# OpAmpBreakout-fragmentC.net
KiCad netlist of a schematic drawn in EAGLE
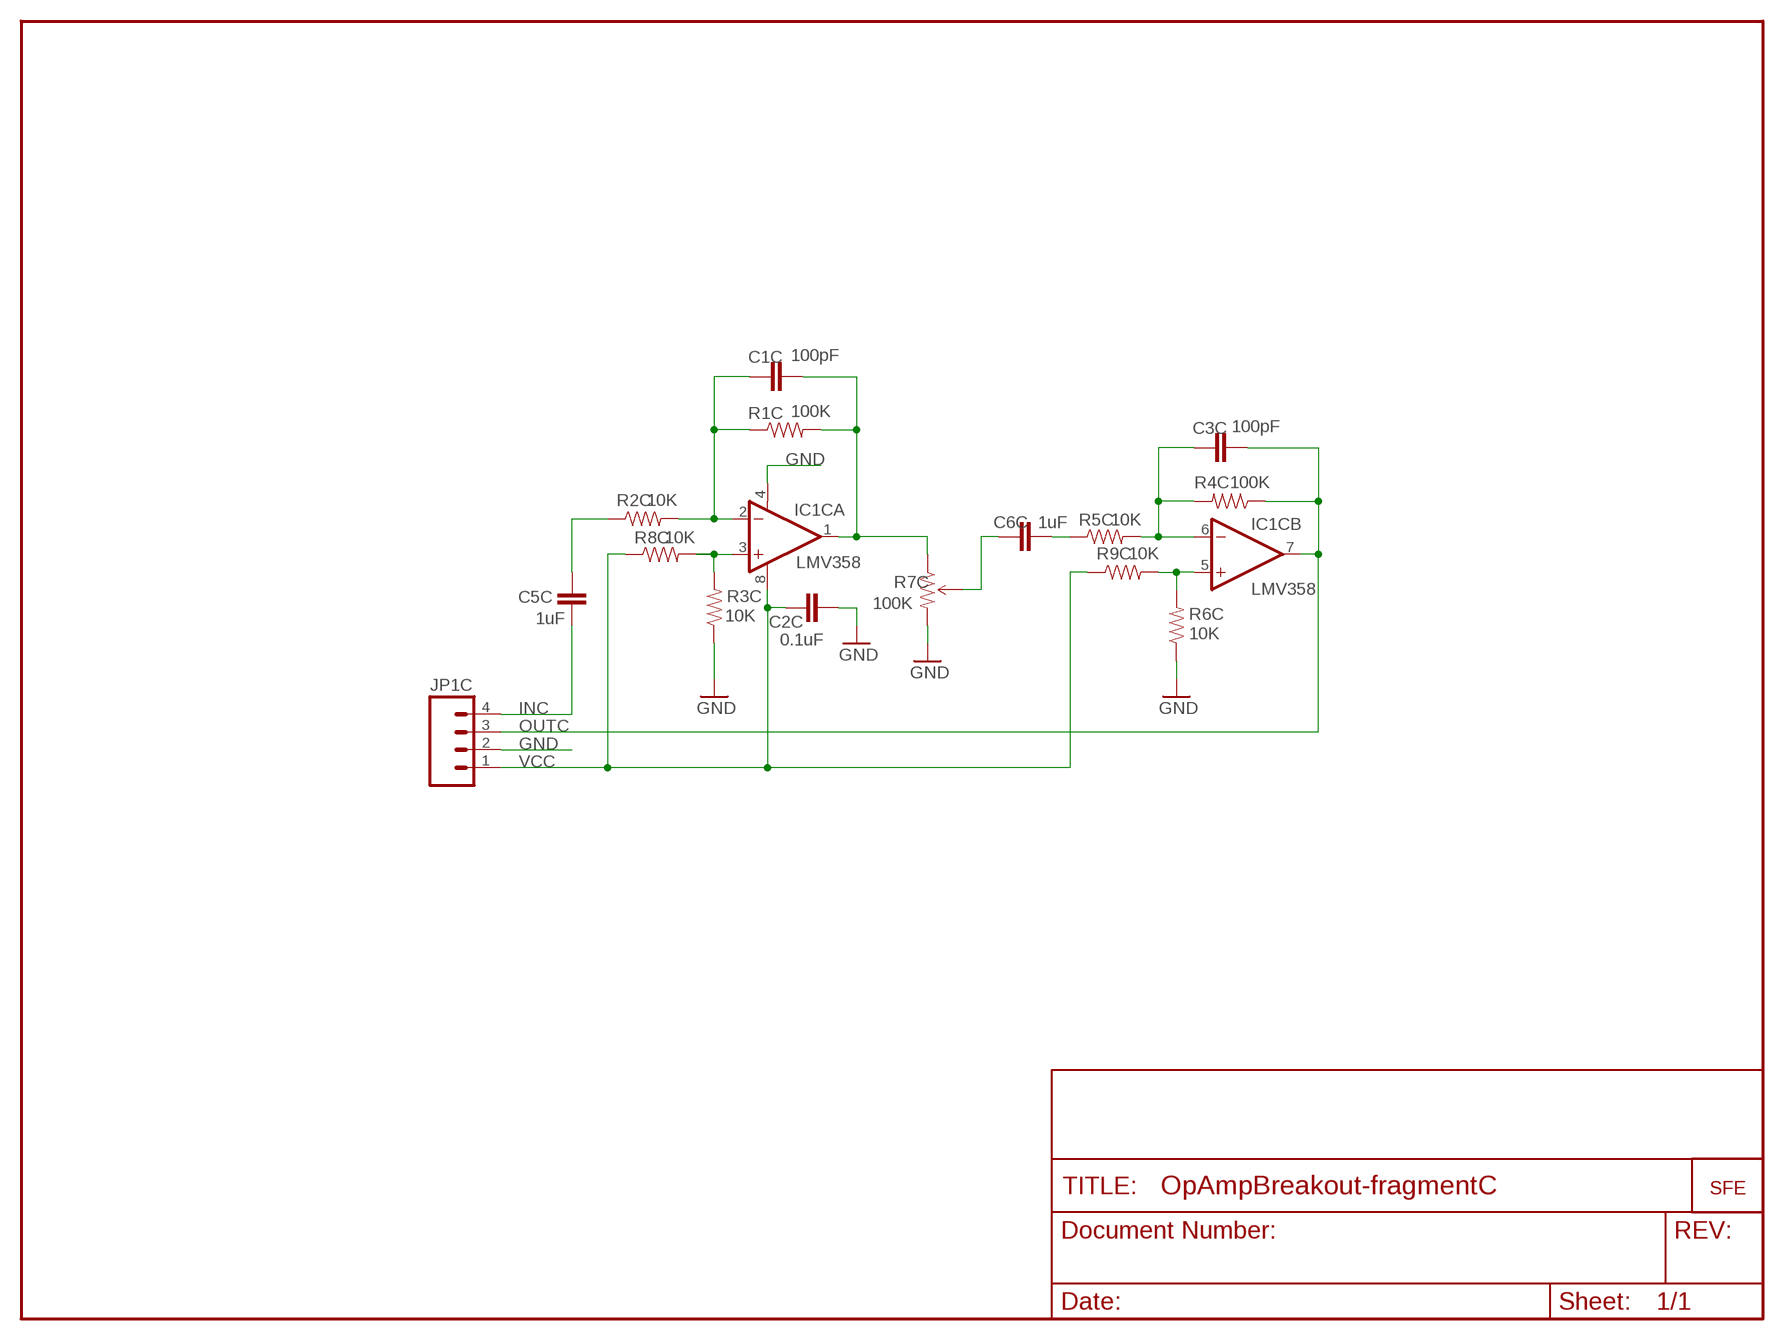
[diagram p0: schematic, sheet 1]

(export (version "E")
  (design (tool "Eeschema 10.0.6"))
  (components
    (comp (ref "C1C")
      (value "100pF")
      (footprint "eagle-import:C0402")
      (libsource (lib "eagle-import") (part "CAP0402"))
    )
    (comp (ref "C2C")
      (value "0.1uF")
      (footprint "eagle-import:C0402")
      (libsource (lib "eagle-import") (part "CAP0402"))
    )
    (comp (ref "C3C")
      (value "100pF")
      (footprint "eagle-import:C0402")
      (libsource (lib "eagle-import") (part "CAP0402"))
    )
    (comp (ref "C5C")
      (value "1uF")
      (footprint "eagle-import:C0402")
      (libsource (lib "eagle-import") (part "CAP0402"))
    )
    (comp (ref "C6C")
      (value "1uF")
      (footprint "eagle-import:C0402")
      (libsource (lib "eagle-import") (part "CAP0402"))
    )
    (comp (ref "IC1C")
      (value "LMV358")
      (footprint "eagle-import:SO08")
      (libsource (lib "eagle-import") (part "OPAMP-DUALU"))
    )
    (comp (ref "JP1C")
      (value "M04PTH")
      (footprint "eagle-import:1X04")
      (libsource (lib "eagle-import") (part "M04PTH"))
    )
    (comp (ref "R1C")
      (value "100K")
      (footprint "eagle-import:C0402")
      (libsource (lib "eagle-import") (part "RESISTOR0402"))
    )
    (comp (ref "R2C")
      (value "10K")
      (footprint "eagle-import:C0402")
      (libsource (lib "eagle-import") (part "RESISTOR0402"))
    )
    (comp (ref "R3C")
      (value "10K")
      (footprint "eagle-import:C0402")
      (libsource (lib "eagle-import") (part "RESISTOR0402"))
    )
    (comp (ref "R4C")
      (value "100K")
      (footprint "eagle-import:C0402")
      (libsource (lib "eagle-import") (part "RESISTOR0402"))
    )
    (comp (ref "R5C")
      (value "10K")
      (footprint "eagle-import:C0402")
      (libsource (lib "eagle-import") (part "RESISTOR0402"))
    )
    (comp (ref "R6C")
      (value "10K")
      (footprint "eagle-import:C0402")
      (libsource (lib "eagle-import") (part "RESISTOR0402"))
    )
    (comp (ref "R7C")
      (value "100K")
      (footprint "eagle-import:TRIMPOT-3MM")
      (libsource (lib "eagle-import") (part "TRIMPOTSMD"))
    )
    (comp (ref "R8C")
      (value "10K")
      (footprint "eagle-import:C0402")
      (libsource (lib "eagle-import") (part "SparkFun-DC_RESISTOR0402"))
    )
    (comp (ref "R9C")
      (value "10K")
      (footprint "eagle-import:C0402")
      (libsource (lib "eagle-import") (part "SparkFun-DC_RESISTOR0402"))
    )
    (comp (ref "U$3C")
      (value "LOGO-SFENEW")
      (footprint "eagle-import:SFE-NEW-WEBLOGO")
      (libsource (lib "eagle-import") (part "LOGO-SFENEW"))
    )
  )
  (nets
    (net (code "1") (name "/INC") (class "Default")
      (node (ref "C5C") (pin "1") (pinfunction "1_1") (pintype "passive"))
      (node (ref "JP1C") (pin "4") (pinfunction "4_4") (pintype "passive"))
    )
    (net (code "2") (name "/OUTC") (class "Default")
      (node (ref "C3C") (pin "2") (pinfunction "2_2") (pintype "passive"))
      (node (ref "IC1C") (pin "7") (pinfunction "OUT_7") (pintype "output"))
      (node (ref "JP1C") (pin "3") (pinfunction "3_3") (pintype "passive"))
      (node (ref "R4C") (pin "1") (pinfunction "1_1") (pintype "passive"))
    )
    (net (code "3") (name "/VCC") (class "Default")
      (node (ref "C2C") (pin "1") (pinfunction "1_1") (pintype "passive"))
      (node (ref "IC1C") (pin "8") (pinfunction "V+_8") (pintype "power_in"))
      (node (ref "JP1C") (pin "1") (pinfunction "1_1") (pintype "passive"))
      (node (ref "R8C") (pin "1") (pinfunction "1_1") (pintype "passive"))
      (node (ref "R9C") (pin "1") (pinfunction "1_1") (pintype "passive"))
    )
    (net (code "4") (name "GND") (class "Default")
      (node (ref "C2C") (pin "2") (pinfunction "2_2") (pintype "passive"))
      (node (ref "IC1C") (pin "4") (pinfunction "V-_4") (pintype "power_in"))
      (node (ref "JP1C") (pin "2") (pinfunction "2_2") (pintype "passive"))
      (node (ref "R3C") (pin "1") (pinfunction "1_1") (pintype "passive"))
      (node (ref "R6C") (pin "1") (pinfunction "1_1") (pintype "passive"))
      (node (ref "R7C") (pin "3") (pinfunction "CW_3") (pintype "passive"))
    )
    (net (code "5") (name "Net-(C5C-Pad2)") (class "Default")
      (node (ref "C5C") (pin "2") (pinfunction "2_2") (pintype "passive"))
      (node (ref "R2C") (pin "1") (pinfunction "1_1") (pintype "passive"))
    )
    (net (code "6") (name "Net-(C6C-Pad1)") (class "Default")
      (node (ref "C6C") (pin "1") (pinfunction "1_1") (pintype "passive"))
      (node (ref "R5C") (pin "1") (pinfunction "1_1") (pintype "passive"))
    )
    (net (code "7") (name "Net-(IC1CA-+IN)") (class "Default")
      (node (ref "IC1C") (pin "3") (pinfunction "+IN_3") (pintype "input"))
      (node (ref "R3C") (pin "2") (pinfunction "2_2") (pintype "passive"))
      (node (ref "R8C") (pin "2") (pinfunction "2_2") (pintype "passive"))
    )
    (net (code "8") (name "Net-(IC1CA--IN)") (class "Default")
      (node (ref "C1C") (pin "1") (pinfunction "1_1") (pintype "passive"))
      (node (ref "IC1C") (pin "2") (pinfunction "-IN_2") (pintype "input"))
      (node (ref "R1C") (pin "1") (pinfunction "1_1") (pintype "passive"))
      (node (ref "R2C") (pin "2") (pinfunction "2_2") (pintype "passive"))
    )
    (net (code "9") (name "Net-(IC1CA-OUT)") (class "Default")
      (node (ref "C1C") (pin "2") (pinfunction "2_2") (pintype "passive"))
      (node (ref "IC1C") (pin "1") (pinfunction "OUT_1") (pintype "output"))
      (node (ref "R1C") (pin "2") (pinfunction "2_2") (pintype "passive"))
      (node (ref "R7C") (pin "1") (pinfunction "CCW_1") (pintype "passive"))
    )
    (net (code "10") (name "Net-(IC1CB-+IN)") (class "Default")
      (node (ref "IC1C") (pin "5") (pinfunction "+IN_5") (pintype "input"))
      (node (ref "R6C") (pin "2") (pinfunction "2_2") (pintype "passive"))
      (node (ref "R9C") (pin "2") (pinfunction "2_2") (pintype "passive"))
    )
    (net (code "11") (name "Net-(IC1CB--IN)") (class "Default")
      (node (ref "C3C") (pin "1") (pinfunction "1_1") (pintype "passive"))
      (node (ref "IC1C") (pin "6") (pinfunction "-IN_6") (pintype "input"))
      (node (ref "R4C") (pin "2") (pinfunction "2_2") (pintype "passive"))
      (node (ref "R5C") (pin "2") (pinfunction "2_2") (pintype "passive"))
    )
    (net (code "12") (name "Net-(R7C-WIPER)") (class "Default")
      (node (ref "C6C") (pin "2") (pinfunction "2_2") (pintype "passive"))
      (node (ref "R7C") (pin "2") (pinfunction "WIPER_2") (pintype "passive"))
    )
  )
)
